# trippling_v1_2.net
KiCad netlist of a schematic drawn in EAGLE
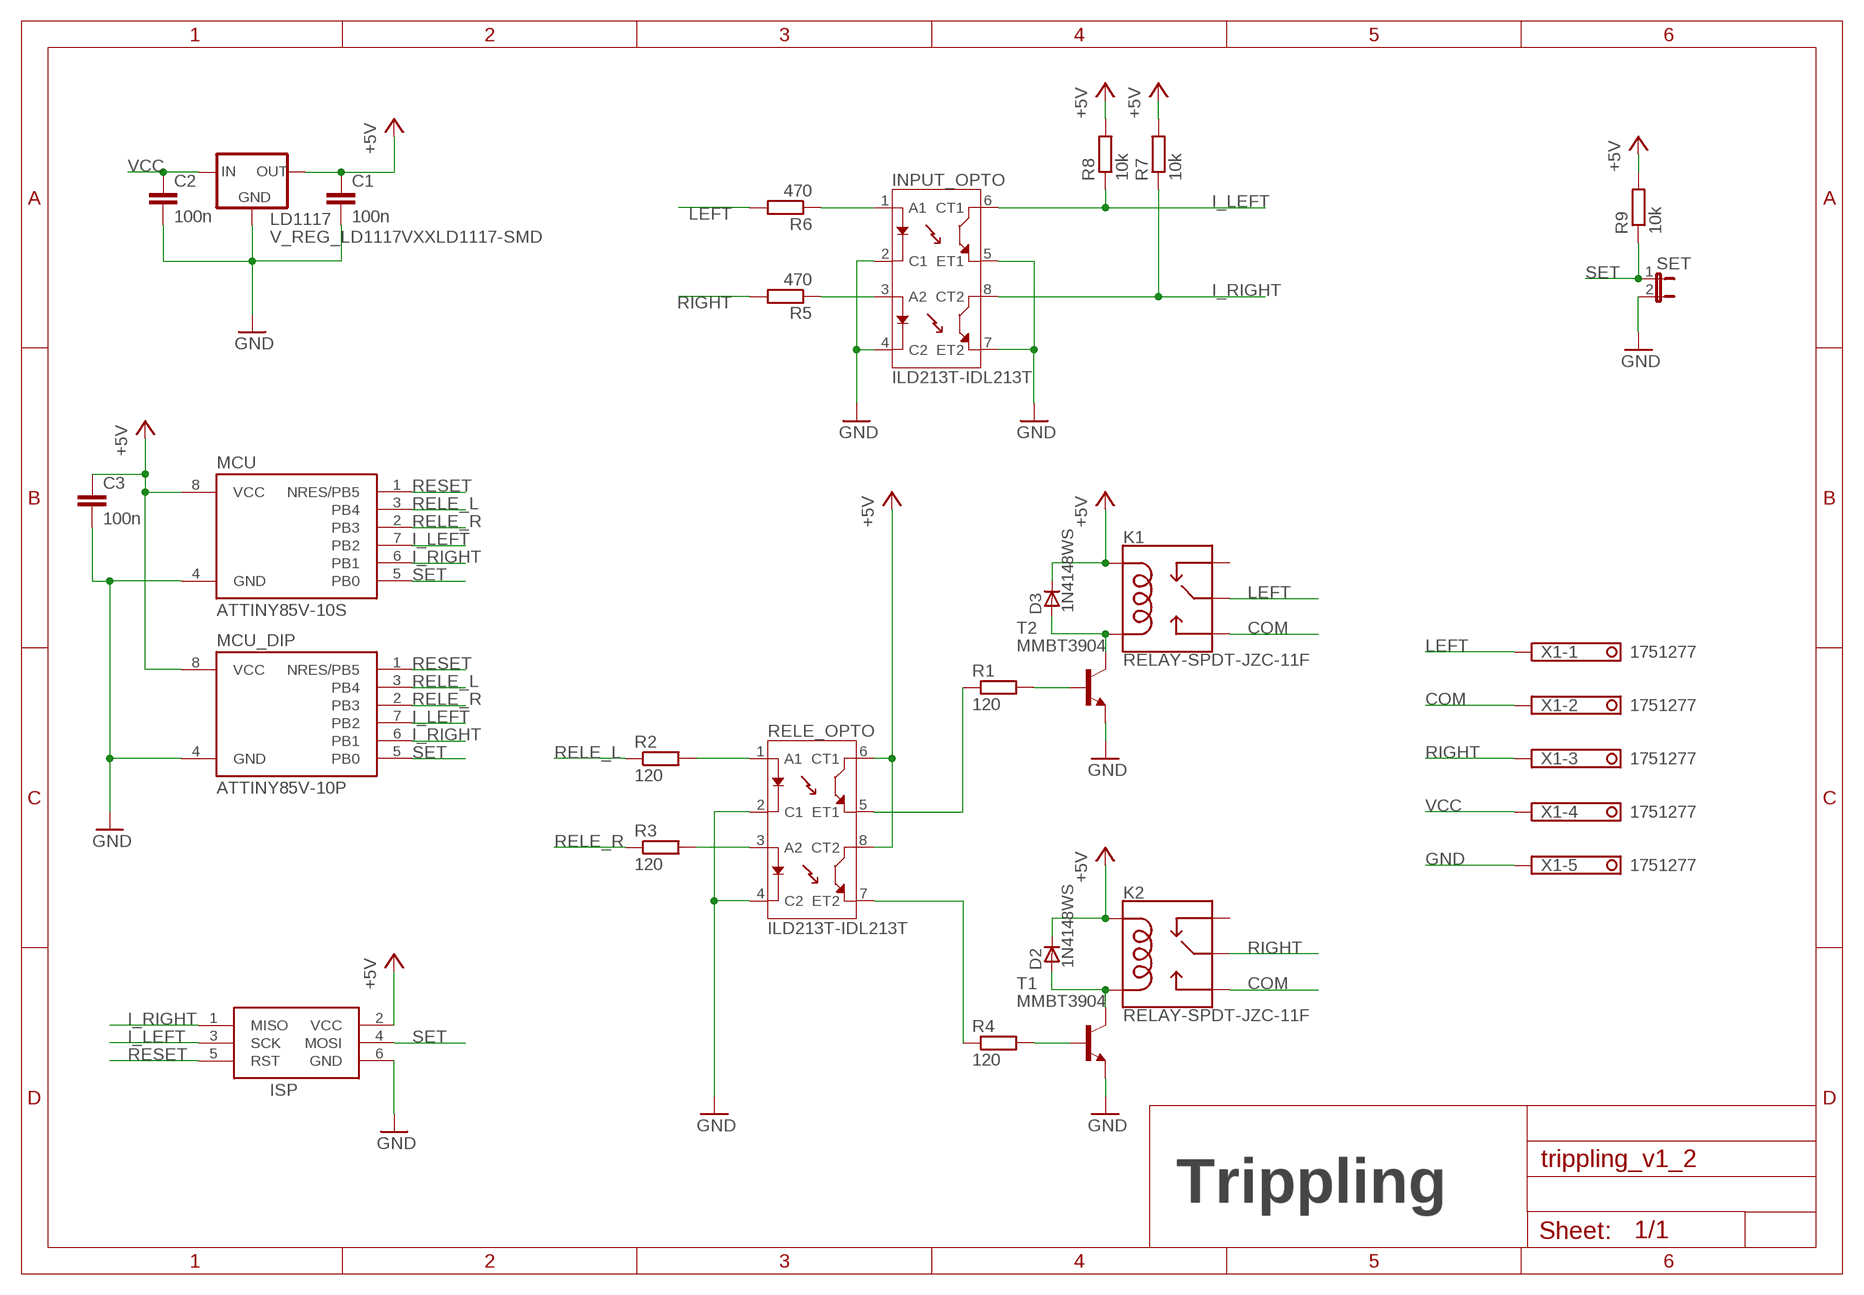
[diagram p0: schematic, sheet 1]

(export (version "E")
  (design (tool "Eeschema 10.0.6"))
  (components
    (comp (ref "C1")
      (value "100n")
      (footprint "eagle-import:C0805")
      (libsource (lib "eagle-import") (part "C-EUC0805"))
    )
    (comp (ref "C2")
      (value "100n")
      (footprint "eagle-import:C0805")
      (libsource (lib "eagle-import") (part "C-EUC0805"))
    )
    (comp (ref "C3")
      (value "100n")
      (footprint "eagle-import:C0805")
      (libsource (lib "eagle-import") (part "C-EUC0805"))
    )
    (comp (ref "D2")
      (value "1N4148WS")
      (footprint "eagle-import:SOD323F")
      (libsource (lib "eagle-import") (part "1N4148WS"))
    )
    (comp (ref "D3")
      (value "1N4148WS")
      (footprint "eagle-import:SOD323F")
      (libsource (lib "eagle-import") (part "1N4148WS"))
    )
    (comp (ref "INPUT_OPTO")
      (value "ILD213T-IDL213T")
      (footprint "eagle-import:SO08")
      (libsource (lib "eagle-import") (part "ILD213T-IDL213T"))
    )
    (comp (ref "ISP")
      (value "AVRISP-6")
      (footprint "eagle-import:AVRISP")
      (libsource (lib "eagle-import") (part "AVRISP-6"))
    )
    (comp (ref "K1")
      (value "RELAY-SPDT-JZC-11F")
      (footprint "eagle-import:RELAY-JZC")
      (libsource (lib "eagle-import") (part "RELAY-SPDT-JZC-11F"))
    )
    (comp (ref "K2")
      (value "RELAY-SPDT-JZC-11F")
      (footprint "eagle-import:RELAY-JZC")
      (libsource (lib "eagle-import") (part "RELAY-SPDT-JZC-11F"))
    )
    (comp (ref "LD1117")
      (value "V_REG_LD1117VXXLD1117-SMD")
      (footprint "eagle-import:SOT223")
      (libsource (lib "eagle-import") (part "V_REG_LD1117VXXLD1117-SMD"))
    )
    (comp (ref "MCU")
      (value "ATTINY85V-10S")
      (footprint "eagle-import:SOIC8_EIAJ_208MIL")
      (libsource (lib "eagle-import") (part "ATTINY85SV-10"))
    )
    (comp (ref "MCU_DIP")
      (value "ATTINY85V-10P")
      (footprint "eagle-import:PDIP08_300MIL")
      (libsource (lib "eagle-import") (part "ATTINY85PV-10"))
    )
    (comp (ref "R1")
      (value "120")
      (footprint "eagle-import:R0805")
      (libsource (lib "eagle-import") (part "R-EU_R0805"))
    )
    (comp (ref "R2")
      (value "120")
      (footprint "eagle-import:R0805")
      (libsource (lib "eagle-import") (part "R-EU_R0805"))
    )
    (comp (ref "R3")
      (value "120")
      (footprint "eagle-import:R0805")
      (libsource (lib "eagle-import") (part "R-EU_R0805"))
    )
    (comp (ref "R4")
      (value "120")
      (footprint "eagle-import:R0805")
      (libsource (lib "eagle-import") (part "R-EU_R0805"))
    )
    (comp (ref "R5")
      (value "470")
      (footprint "eagle-import:R0805")
      (libsource (lib "eagle-import") (part "R-EU_R0805"))
    )
    (comp (ref "R6")
      (value "470")
      (footprint "eagle-import:R0805")
      (libsource (lib "eagle-import") (part "R-EU_R0805"))
    )
    (comp (ref "R7")
      (value "10k")
      (footprint "eagle-import:R0805")
      (libsource (lib "eagle-import") (part "R-EU_R0805"))
    )
    (comp (ref "R8")
      (value "10k")
      (footprint "eagle-import:R0805")
      (libsource (lib "eagle-import") (part "R-EU_R0805"))
    )
    (comp (ref "R9")
      (value "10k")
      (footprint "eagle-import:R0805")
      (libsource (lib "eagle-import") (part "R-EU_R0805"))
    )
    (comp (ref "RELE_OPTO")
      (value "ILD213T-IDL213T")
      (footprint "eagle-import:SO08")
      (libsource (lib "eagle-import") (part "ILD213T-IDL213T"))
    )
    (comp (ref "SET")
      (value "JP1E")
      (footprint "eagle-import:JP1")
      (libsource (lib "eagle-import") (part "JP1E"))
    )
    (comp (ref "T1")
      (value "MMBT3904")
      (footprint "eagle-import:SOT23-BEC")
      (libsource (lib "eagle-import") (part "-NPN-SOT23-BECMMBT3904LT1"))
    )
    (comp (ref "T2")
      (value "MMBT3904")
      (footprint "eagle-import:SOT23-BEC")
      (libsource (lib "eagle-import") (part "-NPN-SOT23-BECMMBT3904LT1"))
    )
    (comp (ref "X1")
      (value "1751277")
      (footprint "eagle-import:1751277")
      (libsource (lib "eagle-import") (part "1751277"))
    )
  )
  (nets
    (net (code "1") (name "+5V") (class "Default")
      (node (ref "C1") (pin "1") (pinfunction "1_1") (pintype "passive"))
      (node (ref "C3") (pin "1") (pinfunction "1_1") (pintype "passive"))
      (node (ref "D2") (pin "C") (pinfunction "C_C") (pintype "passive"))
      (node (ref "D3") (pin "C") (pinfunction "C_C") (pintype "passive"))
      (node (ref "ISP") (pin "2") (pinfunction "VCC_2") (pintype "power_in"))
      (node (ref "K1") (pin "5") (pinfunction "COIL1_5") (pintype "bidirectional"))
      (node (ref "K2") (pin "5") (pinfunction "COIL1_5") (pintype "bidirectional"))
      (node (ref "LD1117") (pin "2") (pinfunction "OUT_2") (pintype "passive"))
      (node (ref "MCU") (pin "8") (pinfunction "VCC_8") (pintype "power_in"))
      (node (ref "MCU_DIP") (pin "8") (pinfunction "VCC_8") (pintype "power_in"))
      (node (ref "R7") (pin "2") (pinfunction "2_2") (pintype "passive"))
      (node (ref "R8") (pin "2") (pinfunction "2_2") (pintype "passive"))
      (node (ref "R9") (pin "2") (pinfunction "2_2") (pintype "passive"))
      (node (ref "RELE_OPTO") (pin "6") (pinfunction "CT1_6") (pintype "bidirectional"))
      (node (ref "RELE_OPTO") (pin "8") (pinfunction "CT2_8") (pintype "bidirectional"))
    )
    (net (code "2") (name "/COM") (class "Default")
      (node (ref "K1") (pin "3") (pinfunction "NO_3") (pintype "bidirectional"))
      (node (ref "K2") (pin "3") (pinfunction "NO_3") (pintype "bidirectional"))
      (node (ref "X1") (pin "2") (pinfunction "K_2") (pintype "passive"))
    )
    (net (code "3") (name "/I_LEFT") (class "Default")
      (node (ref "INPUT_OPTO") (pin "6") (pinfunction "CT1_6") (pintype "bidirectional"))
      (node (ref "ISP") (pin "3") (pinfunction "SCK_3") (pintype "output"))
      (node (ref "MCU") (pin "7") (pinfunction "PB2_7") (pintype "bidirectional"))
      (node (ref "MCU_DIP") (pin "7") (pinfunction "PB2_7") (pintype "bidirectional"))
      (node (ref "R8") (pin "1") (pinfunction "1_1") (pintype "passive"))
    )
    (net (code "4") (name "/I_RIGHT") (class "Default")
      (node (ref "INPUT_OPTO") (pin "8") (pinfunction "CT2_8") (pintype "bidirectional"))
      (node (ref "ISP") (pin "1") (pinfunction "MISO_1") (pintype "input"))
      (node (ref "MCU") (pin "6") (pinfunction "PB1_6") (pintype "bidirectional"))
      (node (ref "MCU_DIP") (pin "6") (pinfunction "PB1_6") (pintype "bidirectional"))
      (node (ref "R7") (pin "1") (pinfunction "1_1") (pintype "passive"))
    )
    (net (code "5") (name "/LEFT") (class "Default")
      (node (ref "K1") (pin "4") (pinfunction "MAIN_4") (pintype "bidirectional"))
      (node (ref "R6") (pin "2") (pinfunction "2_2") (pintype "passive"))
      (node (ref "X1") (pin "1") (pinfunction "K_1") (pintype "passive"))
    )
    (net (code "6") (name "/RELE_L") (class "Default")
      (node (ref "MCU") (pin "3") (pinfunction "PB4_3") (pintype "bidirectional"))
      (node (ref "MCU_DIP") (pin "3") (pinfunction "PB4_3") (pintype "bidirectional"))
      (node (ref "R2") (pin "1") (pinfunction "1_1") (pintype "passive"))
    )
    (net (code "7") (name "/RELE_R") (class "Default")
      (node (ref "MCU") (pin "2") (pinfunction "PB3_2") (pintype "bidirectional"))
      (node (ref "MCU_DIP") (pin "2") (pinfunction "PB3_2") (pintype "bidirectional"))
      (node (ref "R3") (pin "1") (pinfunction "1_1") (pintype "passive"))
    )
    (net (code "8") (name "/RESET") (class "Default")
      (node (ref "ISP") (pin "5") (pinfunction "RST_5") (pintype "output"))
      (node (ref "MCU") (pin "1") (pinfunction "NRES/PB5_1") (pintype "bidirectional"))
      (node (ref "MCU_DIP") (pin "1") (pinfunction "NRES/PB5_1") (pintype "bidirectional"))
    )
    (net (code "9") (name "/RIGHT") (class "Default")
      (node (ref "K2") (pin "4") (pinfunction "MAIN_4") (pintype "bidirectional"))
      (node (ref "R5") (pin "2") (pinfunction "2_2") (pintype "passive"))
      (node (ref "X1") (pin "3") (pinfunction "K_3") (pintype "passive"))
    )
    (net (code "10") (name "/SET") (class "Default")
      (node (ref "ISP") (pin "4") (pinfunction "MOSI_4") (pintype "output"))
      (node (ref "MCU") (pin "5") (pinfunction "PB0_5") (pintype "bidirectional"))
      (node (ref "MCU_DIP") (pin "5") (pinfunction "PB0_5") (pintype "bidirectional"))
      (node (ref "R9") (pin "1") (pinfunction "1_1") (pintype "passive"))
      (node (ref "SET") (pin "1") (pinfunction "1_1") (pintype "passive"))
    )
    (net (code "11") (name "/VCC") (class "Default")
      (node (ref "C2") (pin "1") (pinfunction "1_1") (pintype "passive"))
      (node (ref "LD1117") (pin "3") (pinfunction "IN_3") (pintype "input"))
      (node (ref "X1") (pin "4") (pinfunction "K_4") (pintype "passive"))
    )
    (net (code "12") (name "GND") (class "Default")
      (node (ref "C1") (pin "2") (pinfunction "2_2") (pintype "passive"))
      (node (ref "C2") (pin "2") (pinfunction "2_2") (pintype "passive"))
      (node (ref "C3") (pin "2") (pinfunction "2_2") (pintype "passive"))
      (node (ref "INPUT_OPTO") (pin "2") (pinfunction "C1_2") (pintype "bidirectional"))
      (node (ref "INPUT_OPTO") (pin "4") (pinfunction "C2_4") (pintype "bidirectional"))
      (node (ref "INPUT_OPTO") (pin "5") (pinfunction "ET1_5") (pintype "bidirectional"))
      (node (ref "INPUT_OPTO") (pin "7") (pinfunction "ET2_7") (pintype "bidirectional"))
      (node (ref "ISP") (pin "6") (pinfunction "GND_6") (pintype "power_in"))
      (node (ref "LD1117") (pin "1") (pinfunction "GND_1") (pintype "input"))
      (node (ref "MCU") (pin "4") (pinfunction "GND_4") (pintype "power_in"))
      (node (ref "MCU_DIP") (pin "4") (pinfunction "GND_4") (pintype "power_in"))
      (node (ref "RELE_OPTO") (pin "2") (pinfunction "C1_2") (pintype "bidirectional"))
      (node (ref "RELE_OPTO") (pin "4") (pinfunction "C2_4") (pintype "bidirectional"))
      (node (ref "SET") (pin "2") (pinfunction "2_2") (pintype "passive"))
      (node (ref "T1") (pin "E") (pinfunction "E_E") (pintype "passive"))
      (node (ref "T2") (pin "E") (pinfunction "E_E") (pintype "passive"))
      (node (ref "X1") (pin "5") (pinfunction "K_5") (pintype "passive"))
    )
    (net (code "13") (name "Net-(INPUT_OPTO-A1)") (class "Default")
      (node (ref "INPUT_OPTO") (pin "1") (pinfunction "A1_1") (pintype "bidirectional"))
      (node (ref "R6") (pin "1") (pinfunction "1_1") (pintype "passive"))
    )
    (net (code "14") (name "Net-(INPUT_OPTO-A2)") (class "Default")
      (node (ref "INPUT_OPTO") (pin "3") (pinfunction "A2_3") (pintype "bidirectional"))
      (node (ref "R5") (pin "1") (pinfunction "1_1") (pintype "passive"))
    )
    (net (code "15") (name "Net-(K1-COIL2)") (class "Default")
      (node (ref "D3") (pin "A") (pinfunction "A_A") (pintype "passive"))
      (node (ref "K1") (pin "1") (pinfunction "COIL2_1") (pintype "bidirectional"))
      (node (ref "T2") (pin "C") (pinfunction "C_C") (pintype "passive"))
    )
    (net (code "16") (name "Net-(K2-COIL2)") (class "Default")
      (node (ref "D2") (pin "A") (pinfunction "A_A") (pintype "passive"))
      (node (ref "K2") (pin "1") (pinfunction "COIL2_1") (pintype "bidirectional"))
      (node (ref "T1") (pin "C") (pinfunction "C_C") (pintype "passive"))
    )
    (net (code "17") (name "Net-(R1-Pad2)") (class "Default")
      (node (ref "R1") (pin "2") (pinfunction "2_2") (pintype "passive"))
      (node (ref "T2") (pin "B") (pinfunction "B_B") (pintype "passive"))
    )
    (net (code "18") (name "Net-(R4-Pad2)") (class "Default")
      (node (ref "R4") (pin "2") (pinfunction "2_2") (pintype "passive"))
      (node (ref "T1") (pin "B") (pinfunction "B_B") (pintype "passive"))
    )
    (net (code "19") (name "Net-(RELE_OPTO-A1)") (class "Default")
      (node (ref "R2") (pin "2") (pinfunction "2_2") (pintype "passive"))
      (node (ref "RELE_OPTO") (pin "1") (pinfunction "A1_1") (pintype "bidirectional"))
    )
    (net (code "20") (name "Net-(RELE_OPTO-A2)") (class "Default")
      (node (ref "R3") (pin "2") (pinfunction "2_2") (pintype "passive"))
      (node (ref "RELE_OPTO") (pin "3") (pinfunction "A2_3") (pintype "bidirectional"))
    )
    (net (code "21") (name "Net-(RELE_OPTO-ET1)") (class "Default")
      (node (ref "R1") (pin "1") (pinfunction "1_1") (pintype "passive"))
      (node (ref "RELE_OPTO") (pin "5") (pinfunction "ET1_5") (pintype "bidirectional"))
    )
    (net (code "22") (name "Net-(RELE_OPTO-ET2)") (class "Default")
      (node (ref "R4") (pin "1") (pinfunction "1_1") (pintype "passive"))
      (node (ref "RELE_OPTO") (pin "7") (pinfunction "ET2_7") (pintype "bidirectional"))
    )
    (net (code "23") (name "unconnected-(K1-NC-Pad2)") (class "Default")
      (node (ref "K1") (pin "2") (pinfunction "NC_2") (pintype "bidirectional"))
    )
    (net (code "24") (name "unconnected-(K2-NC-Pad2)") (class "Default")
      (node (ref "K2") (pin "2") (pinfunction "NC_2") (pintype "bidirectional"))
    )
  )
)
